# 8_1_BEACON_DRIVER.net
KiCad netlist of a schematic drawn in Altium Designer
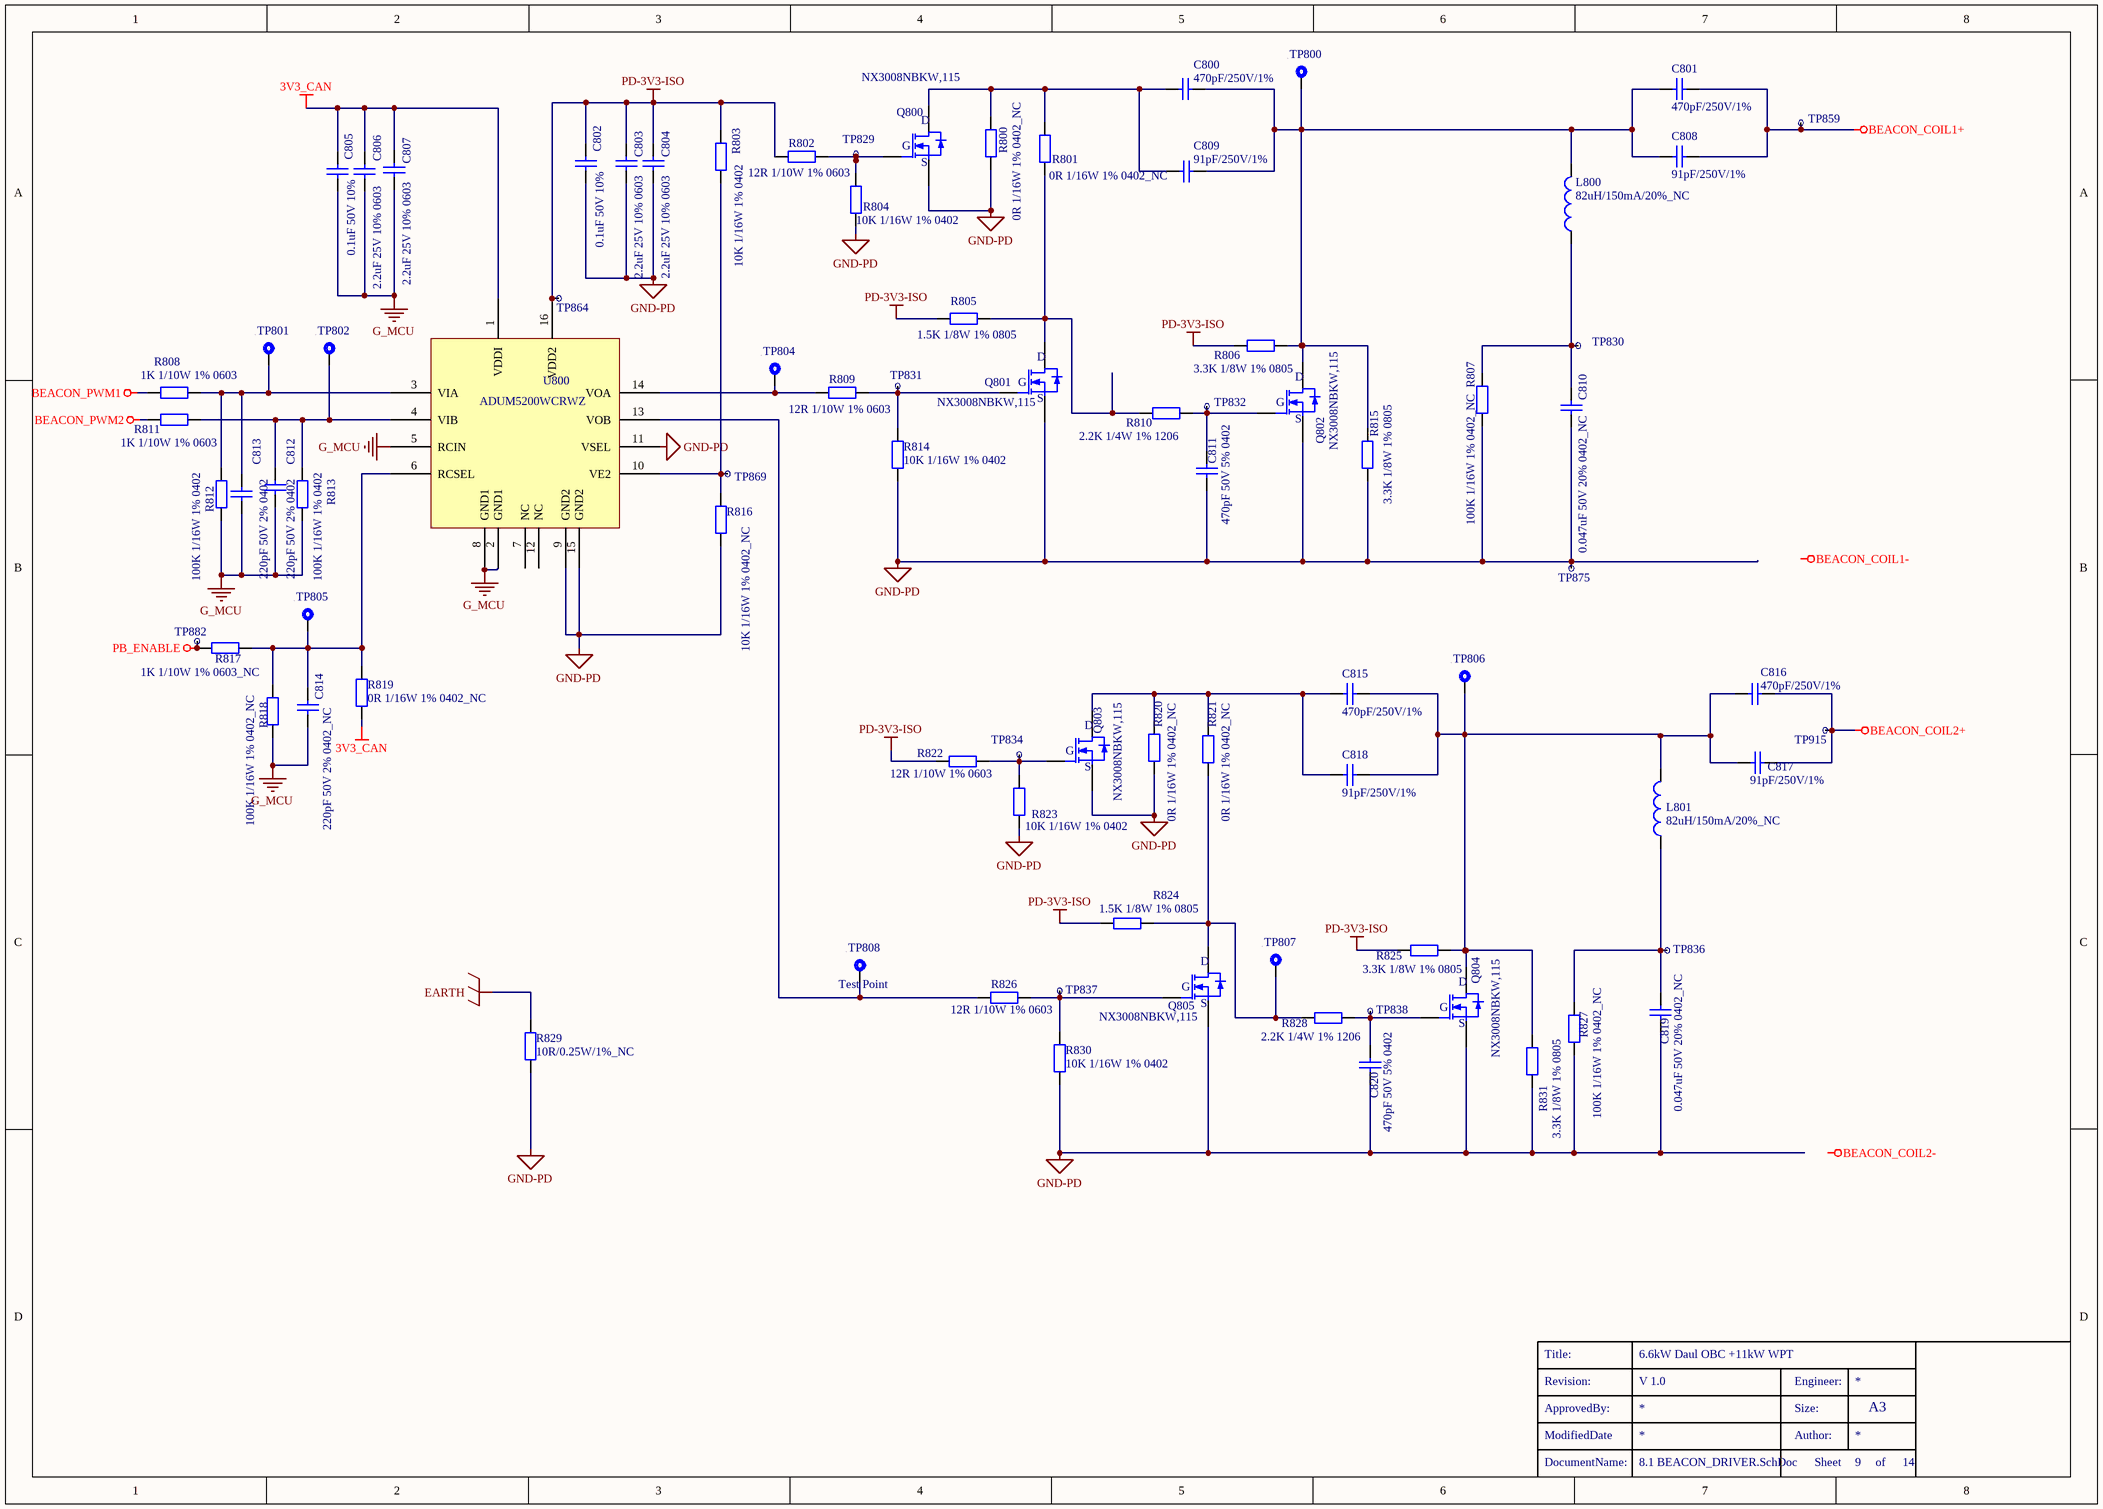
[diagram p0: 8.1 BEACON_DRIVER.SchDoc]

(export (version "E")
  (design (tool "Eeschema 10.0.6"))
  (components
    (comp (ref "C800")
      (value "470pF/250V/1%")
      (footprint "C0603")
      (description "CAP CER 470pF 250V 1% C0G/NP0 0603 SMD")
      (libsource (lib "Miscellaneous Devices") (part "Cap"))
    )
    (comp (ref "C801")
      (value "470pF/250V/1%")
      (footprint "C0603")
      (description "CAP CER 470pF 250V 1% C0G/NP0 0603 SMD")
      (libsource (lib "Miscellaneous Devices") (part "Cap"))
    )
    (comp (ref "C802")
      (value "0.1uF 50V 10%")
      (footprint "C0603")
      (description "CAP CER 0.1uF 50V 10% X7R 0603 SMD")
      (libsource (lib "Miscellaneous Devices") (part "Cap"))
    )
    (comp (ref "C803")
      (value "2.2uF 25V 10% 0603")
      (footprint "C0603")
      (description "CAP CER 2.2uF 25V 10% X5R 0603 SMD")
      (libsource (lib "Miscellaneous Devices") (part "Cap Semi"))
    )
    (comp (ref "C804")
      (value "2.2uF 25V 10% 0603")
      (footprint "C0603")
      (description "CAP CER 2.2uF 25V 10% X5R 0603 SMD")
      (libsource (lib "Miscellaneous Devices") (part "Cap Semi"))
    )
    (comp (ref "C805")
      (value "0.1uF 50V 10%")
      (footprint "C0603")
      (description "CAP CER 0.1uF 50V 10% X7R 0603 SMD")
      (libsource (lib "Miscellaneous Devices") (part "Cap"))
    )
    (comp (ref "C806")
      (value "2.2uF 25V 10% 0603")
      (footprint "C0603")
      (description "CAP CER 2.2uF 25V 10% X5R 0603 SMD")
      (libsource (lib "Miscellaneous Devices") (part "Cap Semi"))
    )
    (comp (ref "C807")
      (value "2.2uF 25V 10% 0603")
      (footprint "C0603")
      (description "CAP CER 2.2uF 25V 10% X5R 0603 SMD")
      (libsource (lib "Miscellaneous Devices") (part "Cap Semi"))
    )
    (comp (ref "C808")
      (value "91pF/250V/1%")
      (footprint "C0603")
      (description "CAP CER 91pF 250V 1% C0G/NP0 0603 SMD")
      (libsource (lib "Miscellaneous Devices") (part "Cap"))
    )
    (comp (ref "C809")
      (value "91pF/250V/1%")
      (footprint "C0603")
      (description "CAP CER 91pF 250V 1% C0G/NP0 0603 SMD")
      (libsource (lib "Miscellaneous Devices") (part "Cap"))
    )
    (comp (ref "C810")
      (value "0.047uF 50V 20% 0402_NC")
      (footprint "C0402")
      (description "CAP CER 0.047uF 50V 20% X7R 0402 SMD")
      (libsource (lib "Miscellaneous Devices") (part "Cap"))
    )
    (comp (ref "C811")
      (value "470pF 50V 5% 0402")
      (footprint "C0402")
      (description "CAP CER 470pF 50V 5% C0G/NP0 0402 SMD")
      (libsource (lib "Miscellaneous Devices") (part "Cap"))
    )
    (comp (ref "C812")
      (value "220pF 50V 2% 0402")
      (footprint "C0402")
      (description "CAP CER 220pF 50V 2% C0G/NPO 0402 SMD")
      (libsource (lib "Miscellaneous Devices") (part "Cap"))
    )
    (comp (ref "C813")
      (value "220pF 50V 2% 0402")
      (footprint "C0402")
      (description "CAP CER 220pF 50V 2% C0G/NPO 0402 SMD")
      (libsource (lib "Miscellaneous Devices") (part "Cap"))
    )
    (comp (ref "C814")
      (value "220pF 50V 2% 0402_NC")
      (footprint "C0402")
      (description "CAP CER 220pF 50V 2% C0G/NPO 0402 SMD")
      (libsource (lib "Miscellaneous Devices") (part "Cap"))
    )
    (comp (ref "C815")
      (value "470pF/250V/1%")
      (footprint "C0603")
      (description "CAP CER 470pF 250V 1% C0G/NP0 0603 SMD")
      (libsource (lib "Miscellaneous Devices") (part "Cap"))
    )
    (comp (ref "C816")
      (value "470pF/250V/1%")
      (footprint "C0603")
      (description "CAP CER 470pF 250V 1% C0G/NP0 0603 SMD")
      (libsource (lib "Miscellaneous Devices") (part "Cap"))
    )
    (comp (ref "C817")
      (value "91pF/250V/1%")
      (footprint "C0603")
      (description "CAP CER 91pF 250V 1% C0G/NP0 0603 SMD")
      (libsource (lib "Miscellaneous Devices") (part "Cap"))
    )
    (comp (ref "C818")
      (value "91pF/250V/1%")
      (footprint "C0603")
      (description "CAP CER 91pF 250V 1% C0G/NP0 0603 SMD")
      (libsource (lib "Miscellaneous Devices") (part "Cap"))
    )
    (comp (ref "C819")
      (value "0.047uF 50V 20% 0402_NC")
      (footprint "C0402")
      (description "CAP CER 0.047uF 50V 20% X7R 0402 SMD")
      (libsource (lib "Miscellaneous Devices") (part "Cap"))
    )
    (comp (ref "C820")
      (value "470pF 50V 5% 0402")
      (footprint "C0402")
      (description "CAP CER 470pF 50V 5% C0G/NP0 0402 SMD")
      (libsource (lib "Miscellaneous Devices") (part "Cap"))
    )
    (comp (ref "L800")
      (value "82uH/150mA/20%_NC")
      (footprint "L2X1.6_0806")
      (description "Inductor 82uH 150mA 20% SMD")
      (libsource (lib "Miscellaneous Devices") (part "Inductor"))
    )
    (comp (ref "L801")
      (value "82uH/150mA/20%_NC")
      (footprint "L2X1.6_0806")
      (description "Inductor 82uH 150mA 20% SMD")
      (libsource (lib "Miscellaneous Devices") (part "Inductor"))
    )
    (comp (ref "Q800")
      (value "NX3008NBKW,115")
      (footprint "SOT323")
      (description "MOSFET N-Channel 30V 350mA SOT-323-3")
      (libsource (lib "N-Channel MOSFET") (part "MOSFET-N"))
    )
    (comp (ref "Q801")
      (value "NX3008NBKW,115")
      (footprint "SOT323")
      (description "MOSFET N-Channel 30V 350mA SOT-323-3")
      (libsource (lib "N-Channel MOSFET") (part "MOSFET-N"))
    )
    (comp (ref "Q802")
      (value "NX3008NBKW,115")
      (footprint "SOT323")
      (description "MOSFET N-Channel 30V 350mA SOT-323-3")
      (libsource (lib "N-Channel MOSFET") (part "MOSFET-N"))
    )
    (comp (ref "Q803")
      (value "NX3008NBKW,115")
      (footprint "SOT323")
      (description "MOSFET N-Channel 30V 350mA SOT-323-3")
      (libsource (lib "N-Channel MOSFET") (part "MOSFET-N"))
    )
    (comp (ref "Q804")
      (value "NX3008NBKW,115")
      (footprint "SOT323")
      (description "MOSFET N-Channel 30V 350mA SOT-323-3")
      (libsource (lib "N-Channel MOSFET") (part "MOSFET-N"))
    )
    (comp (ref "Q805")
      (value "NX3008NBKW,115")
      (footprint "SOT323")
      (description "MOSFET N-Channel 30V 350mA SOT-323-3")
      (libsource (lib "N-Channel MOSFET") (part "MOSFET-N"))
    )
    (comp (ref "R800")
      (value "0R 1/16W 1% 0402_NC")
      (footprint "R0402")
      (description "RES Thick Film 0R 1/16W 1% 0402 SMD")
      (libsource (lib "") (part "Res2_3"))
    )
    (comp (ref "R801")
      (value "0R 1/16W 1% 0402_NC")
      (footprint "R0402")
      (description "RES Thick Film 0R 1/16W 1% 0402 SMD")
      (libsource (lib "") (part "Res2_3"))
    )
    (comp (ref "R802")
      (value "12R 1/10W 1% 0603")
      (footprint "R0603")
      (description "RES Thick Film 12R 1/10W 1% 0603 SMD")
      (libsource (lib "") (part "Res2_1"))
    )
    (comp (ref "R803")
      (value "10K 1/16W 1% 0402")
      (footprint "R0402")
      (description "RES Thick Film 10K 1/16W 1% 0402 SMD")
      (libsource (lib "Miscellaneous Devices") (part "Res2"))
    )
    (comp (ref "R804")
      (value "10K 1/16W 1% 0402")
      (footprint "R0402")
      (description "RES Thick Film 10K 1/16W 1% 0402 SMD")
      (libsource (lib "Miscellaneous Devices") (part "Res2"))
    )
    (comp (ref "R805")
      (value "1.5K 1/8W 1% 0805")
      (footprint "R0805")
      (description "RES Thick Film 1.5K 1/8W 1% 0805 SMD")
      (libsource (lib "") (part "Res2_1"))
    )
    (comp (ref "R806")
      (value "3.3K 1/8W 1% 0805")
      (footprint "R0805")
      (description "RES Thick Film 3.3K 1/8W 1% 0805 SMD")
      (libsource (lib "") (part "Res2_1"))
    )
    (comp (ref "R807")
      (value "100K 1/16W 1% 0402_NC")
      (footprint "R0402")
      (description "RES 100K 1/16W 1% 0402 SMD")
      (libsource (lib "Miscellaneous Devices") (part "Res2"))
    )
    (comp (ref "R808")
      (value "1K 1/10W 1% 0603")
      (footprint "R0603")
      (description "RES Thick Film 1K 1/10W 1% 0603 SMD")
      (libsource (lib "") (part "Res2_2"))
    )
    (comp (ref "R809")
      (value "12R 1/10W 1% 0603")
      (footprint "R0603")
      (description "RES Thick Film 12R 1/10W 1% 0603 SMD")
      (libsource (lib "") (part "Res2_1"))
    )
    (comp (ref "R810")
      (value "2.2K 1/4W 1% 1206")
      (footprint "R1206")
      (description "RES Thick Film 2.2K 1/4W 1% 1206 SMD")
      (libsource (lib "") (part "Res2_1"))
    )
    (comp (ref "R811")
      (value "1K 1/10W 1% 0603")
      (footprint "R0603")
      (description "RES Thick Film 1K 1/10W 1% 0603 SMD")
      (libsource (lib "") (part "Res2_2"))
    )
    (comp (ref "R812")
      (value "100K 1/16W 1% 0402")
      (footprint "R0402")
      (description "RES 100K 1/16W 1% 0402 SMD")
      (libsource (lib "Miscellaneous Devices") (part "Res2"))
    )
    (comp (ref "R813")
      (value "100K 1/16W 1% 0402")
      (footprint "R0402")
      (description "RES 100K 1/16W 1% 0402 SMD")
      (libsource (lib "Miscellaneous Devices") (part "Res2"))
    )
    (comp (ref "R814")
      (value "10K 1/16W 1% 0402")
      (footprint "R0402")
      (description "RES Thick Film 10K 1/16W 1% 0402 SMD")
      (libsource (lib "Miscellaneous Devices") (part "Res2"))
    )
    (comp (ref "R815")
      (value "3.3K 1/8W 1% 0805")
      (footprint "R0805")
      (description "RES Thick Film 3.3K 1/8W 1% 0805 SMD")
      (libsource (lib "Miscellaneous Devices") (part "Res2"))
    )
    (comp (ref "R816")
      (value "10K 1/16W 1% 0402_NC")
      (footprint "R0402")
      (description "RES Thick Film 10K 1/16W 1% 0402 SMD")
      (libsource (lib "Miscellaneous Devices") (part "Res2"))
    )
    (comp (ref "R817")
      (value "1K 1/10W 1% 0603_NC")
      (footprint "R0603")
      (description "RES Thick Film 1K 1/10W 1% 0603 SMD")
      (libsource (lib "") (part "Res2_2"))
    )
    (comp (ref "R818")
      (value "100K 1/16W 1% 0402_NC")
      (footprint "R0402")
      (description "RES 100K 1/16W 1% 0402 SMD")
      (libsource (lib "Miscellaneous Devices") (part "Res2"))
    )
    (comp (ref "R819")
      (value "0R 1/16W 1% 0402_NC")
      (footprint "R0402")
      (description "RES Thick Film 0R 1/16W 1% 0402 SMD")
      (libsource (lib "") (part "Res2_3"))
    )
    (comp (ref "R820")
      (value "0R 1/16W 1% 0402_NC")
      (footprint "R0402")
      (description "RES Thick Film 0R 1/16W 1% 0402 SMD")
      (libsource (lib "") (part "Res2_3"))
    )
    (comp (ref "R821")
      (value "0R 1/16W 1% 0402_NC")
      (footprint "R0402")
      (description "RES Thick Film 0R 1/16W 1% 0402 SMD")
      (libsource (lib "") (part "Res2_3"))
    )
    (comp (ref "R822")
      (value "12R 1/10W 1% 0603")
      (footprint "R0603")
      (description "RES Thick Film 12R 1/10W 1% 0603 SMD")
      (libsource (lib "") (part "Res2_1"))
    )
    (comp (ref "R823")
      (value "10K 1/16W 1% 0402")
      (footprint "R0402")
      (description "RES Thick Film 10K 1/16W 1% 0402 SMD")
      (libsource (lib "Miscellaneous Devices") (part "Res2"))
    )
    (comp (ref "R824")
      (value "1.5K 1/8W 1% 0805")
      (footprint "R0805")
      (description "RES Thick Film 1.5K 1/8W 1% 0805 SMD")
      (libsource (lib "") (part "Res2_1"))
    )
    (comp (ref "R825")
      (value "3.3K 1/8W 1% 0805")
      (footprint "R0805")
      (description "RES Thick Film 3.3K 1/8W 1% 0805 SMD")
      (libsource (lib "") (part "Res2_1"))
    )
    (comp (ref "R826")
      (value "12R 1/10W 1% 0603")
      (footprint "R0603")
      (description "RES Thick Film 12R 1/10W 1% 0603 SMD")
      (libsource (lib "") (part "Res2_1"))
    )
    (comp (ref "R827")
      (value "100K 1/16W 1% 0402_NC")
      (footprint "R0402")
      (description "RES 100K 1/16W 1% 0402 SMD")
      (libsource (lib "Miscellaneous Devices") (part "Res2"))
    )
    (comp (ref "R828")
      (value "2.2K 1/4W 1% 1206")
      (footprint "R1206")
      (description "RES Thick Film 2.2K 1/4W 1% 1206 SMD")
      (libsource (lib "") (part "Res2_1"))
    )
    (comp (ref "R829")
      (value "10R/0.25W/1%_NC")
      (footprint "R1206")
      (description "RES Thick Film 10R 1/4W 1% 1206 SMD")
      (libsource (lib "") (part "Res2_3"))
    )
    (comp (ref "R830")
      (value "10K 1/16W 1% 0402")
      (footprint "R0402")
      (description "RES Thick Film 10K 1/16W 1% 0402 SMD")
      (libsource (lib "Miscellaneous Devices") (part "Res2"))
    )
    (comp (ref "R831")
      (value "3.3K 1/8W 1% 0805")
      (footprint "R0805")
      (description "RES Thick Film 3.3K 1/8W 1% 0805 SMD")
      (libsource (lib "Miscellaneous Devices") (part "Res2"))
    )
    (comp (ref "TP800")
      (value "Test Point")
      (footprint "测试点")
      (description "Test Point 1mm")
      (libsource (lib "Test Point") (part "Test Point"))
    )
    (comp (ref "TP801")
      (value "Test Point")
      (footprint "测试点")
      (description "Test Point 1mm")
      (libsource (lib "Test Point") (part "Test Point"))
    )
    (comp (ref "TP802")
      (value "Test Point")
      (footprint "测试点")
      (description "Test Point 1mm")
      (libsource (lib "Test Point") (part "Test Point"))
    )
    (comp (ref "TP804")
      (value "Test Point")
      (footprint "测试点")
      (description "Test Point 1mm")
      (libsource (lib "Test Point") (part "Test Point"))
    )
    (comp (ref "TP805")
      (value "Test Point")
      (footprint "测试点")
      (description "Test Point 1mm")
      (libsource (lib "Test Point") (part "Test Point"))
    )
    (comp (ref "TP806")
      (value "Test Point")
      (footprint "测试点")
      (description "Test Point 1mm")
      (libsource (lib "Test Point") (part "Test Point"))
    )
    (comp (ref "TP807")
      (value "Test Point")
      (footprint "测试点")
      (description "Test Point 1mm")
      (libsource (lib "Test Point") (part "Test Point"))
    )
    (comp (ref "TP808")
      (value "Test Point")
      (footprint "测试点")
      (description "Test Point 1mm")
      (libsource (lib "Test Point") (part "Test Point"))
    )
    (comp (ref "TP829") (value "测试点") (footprint "测试点") (libsource (lib "原理图符号库2.0") (part "测试点")))
    (comp (ref "TP830") (value "测试点") (footprint "测试点") (libsource (lib "原理图符号库2.0") (part "测试点")))
    (comp (ref "TP831") (value "测试点") (footprint "测试点") (libsource (lib "原理图符号库2.0") (part "测试点")))
    (comp (ref "TP832") (value "测试点") (footprint "测试点") (libsource (lib "原理图符号库2.0") (part "测试点")))
    (comp (ref "TP834") (value "测试点") (footprint "测试点") (libsource (lib "原理图符号库2.0") (part "测试点")))
    (comp (ref "TP836") (value "测试点") (footprint "测试点") (libsource (lib "原理图符号库2.0") (part "测试点")))
    (comp (ref "TP837") (value "测试点") (footprint "测试点") (libsource (lib "原理图符号库2.0") (part "测试点")))
    (comp (ref "TP838") (value "测试点") (footprint "测试点") (libsource (lib "原理图符号库2.0") (part "测试点")))
    (comp (ref "TP859") (value "测试点") (footprint "测试点") (libsource (lib "原理图符号库2.0") (part "测试点")))
    (comp (ref "TP864") (value "测试点") (footprint "测试点") (libsource (lib "原理图符号库2.0") (part "测试点")))
    (comp (ref "TP869") (value "测试点") (footprint "测试点") (libsource (lib "原理图符号库2.0") (part "测试点")))
    (comp (ref "TP875") (value "测试点") (footprint "测试点") (libsource (lib "原理图符号库2.0") (part "测试点")))
    (comp (ref "TP882") (value "测试点") (footprint "测试点") (libsource (lib "原理图符号库2.0") (part "测试点")))
    (comp (ref "TP915") (value "测试点") (footprint "测试点") (libsource (lib "原理图符号库2.0") (part "测试点")))
    (comp (ref "U800")
      (value "ADUM5200WCRWZ")
      (footprint "SOIC-16_L10.3-W7.5-P1.27-LS10.3-BL")
      (description "IC Digital Isolator Integrated DC-DC Dual-Channel 3V-5.5V 23mA SOIC-16")
      (libsource (lib "ADUM5200WCRWZ") (part "ADUM5200WCRWZ"))
    )
  )
  (nets
    (net (code "1") (name "3V3_CAN") (class "Default")
      (node (ref "C805") (pin "2") (pinfunction "2_2") (pintype "passive"))
      (node (ref "C806") (pin "2") (pinfunction "2_2") (pintype "passive"))
      (node (ref "C807") (pin "2") (pinfunction "2_2") (pintype "passive"))
      (node (ref "R819") (pin "2") (pinfunction "2_2") (pintype "passive"))
      (node (ref "U800") (pin "1") (pinfunction "VDDI_1") (pintype "passive"))
    )
    (net (code "2") (name "BEACON_COIL1+") (class "Default")
      (node (ref "C801") (pin "1") (pinfunction "1_1") (pintype "passive"))
      (node (ref "C808") (pin "1") (pinfunction "1_1") (pintype "passive"))
      (node (ref "TP859") (pin "1") (pinfunction "1_1") (pintype "passive"))
    )
    (net (code "4") (name "BEACON_COIL2+") (class "Default")
      (node (ref "C816") (pin "1") (pinfunction "1_1") (pintype "passive"))
      (node (ref "C817") (pin "1") (pinfunction "1_1") (pintype "passive"))
      (node (ref "TP915") (pin "1") (pinfunction "1_1") (pintype "passive"))
    )
    (net (code "6") (name "BEACON_PWM1") (class "Default")
      (node (ref "R808") (pin "1") (pinfunction "1_1") (pintype "passive"))
    )
    (net (code "7") (name "BEACON_PWM2") (class "Default")
      (node (ref "R811") (pin "1") (pinfunction "1_1") (pintype "passive"))
    )
    (net (code "8") (name "EARTH") (class "Default")
      (node (ref "R829") (pin "1") (pinfunction "1_1") (pintype "passive"))
    )
    (net (code "9") (name "GND-PD") (class "Default")
      (node (ref "C802") (pin "1") (pinfunction "1_1") (pintype "passive"))
      (node (ref "C803") (pin "1") (pinfunction "1_1") (pintype "passive"))
      (node (ref "C804") (pin "1") (pinfunction "1_1") (pintype "passive"))
      (node (ref "C810") (pin "2") (pinfunction "2_2") (pintype "passive"))
      (node (ref "C811") (pin "2") (pinfunction "2_2") (pintype "passive"))
      (node (ref "C819") (pin "2") (pinfunction "2_2") (pintype "passive"))
      (node (ref "C820") (pin "2") (pinfunction "2_2") (pintype "passive"))
      (node (ref "Q800") (pin "S") (pinfunction "S_S") (pintype "passive"))
      (node (ref "Q801") (pin "S") (pinfunction "S_S") (pintype "passive"))
      (node (ref "Q802") (pin "S") (pinfunction "S_S") (pintype "passive"))
      (node (ref "Q803") (pin "S") (pinfunction "S_S") (pintype "passive"))
      (node (ref "Q804") (pin "S") (pinfunction "S_S") (pintype "passive"))
      (node (ref "Q805") (pin "S") (pinfunction "S_S") (pintype "passive"))
      (node (ref "R800") (pin "2") (pinfunction "2_2") (pintype "passive"))
      (node (ref "R804") (pin "1") (pinfunction "1_1") (pintype "passive"))
      (node (ref "R807") (pin "1") (pinfunction "1_1") (pintype "passive"))
      (node (ref "R814") (pin "1") (pinfunction "1_1") (pintype "passive"))
      (node (ref "R815") (pin "1") (pinfunction "1_1") (pintype "passive"))
      (node (ref "R816") (pin "1") (pinfunction "1_1") (pintype "passive"))
      (node (ref "R820") (pin "2") (pinfunction "2_2") (pintype "passive"))
      (node (ref "R823") (pin "1") (pinfunction "1_1") (pintype "passive"))
      (node (ref "R827") (pin "1") (pinfunction "1_1") (pintype "passive"))
      (node (ref "R829") (pin "2") (pinfunction "2_2") (pintype "passive"))
      (node (ref "R830") (pin "1") (pinfunction "1_1") (pintype "passive"))
      (node (ref "R831") (pin "1") (pinfunction "1_1") (pintype "passive"))
      (node (ref "TP875") (pin "1") (pinfunction "1_1") (pintype "passive"))
      (node (ref "U800") (pin "11") (pinfunction "VSEL_11") (pintype "passive"))
      (node (ref "U800") (pin "15") (pinfunction "GND2_15") (pintype "passive"))
      (node (ref "U800") (pin "9") (pinfunction "GND2_9") (pintype "passive"))
    )
    (net (code "10") (name "G_MCU") (class "Default")
      (node (ref "C805") (pin "1") (pinfunction "1_1") (pintype "passive"))
      (node (ref "C806") (pin "1") (pinfunction "1_1") (pintype "passive"))
      (node (ref "C807") (pin "1") (pinfunction "1_1") (pintype "passive"))
      (node (ref "C812") (pin "2") (pinfunction "2_2") (pintype "passive"))
      (node (ref "C813") (pin "2") (pinfunction "2_2") (pintype "passive"))
      (node (ref "C814") (pin "2") (pinfunction "2_2") (pintype "passive"))
      (node (ref "R812") (pin "1") (pinfunction "1_1") (pintype "passive"))
      (node (ref "R813") (pin "1") (pinfunction "1_1") (pintype "passive"))
      (node (ref "R818") (pin "1") (pinfunction "1_1") (pintype "passive"))
      (node (ref "U800") (pin "2") (pinfunction "GND1_2") (pintype "passive"))
      (node (ref "U800") (pin "5") (pinfunction "RCIN_5") (pintype "passive"))
      (node (ref "U800") (pin "8") (pinfunction "GND1_8") (pintype "passive"))
    )
    (net (code "11") (name "Net-(C800-Pad1)") (class "Default")
      (node (ref "C800") (pin "1") (pinfunction "1_1") (pintype "passive"))
      (node (ref "C801") (pin "2") (pinfunction "2_2") (pintype "passive"))
      (node (ref "C808") (pin "2") (pinfunction "2_2") (pintype "passive"))
      (node (ref "C809") (pin "1") (pinfunction "1_1") (pintype "passive"))
      (node (ref "L800") (pin "2") (pinfunction "2_2") (pintype "passive"))
      (node (ref "Q802") (pin "D") (pinfunction "D_D") (pintype "passive"))
      (node (ref "R806") (pin "1") (pinfunction "1_1") (pintype "passive"))
      (node (ref "R815") (pin "2") (pinfunction "2_2") (pintype "passive"))
      (node (ref "TP800") (pin "1") (pintype "passive"))
    )
    (net (code "12") (name "Net-(C800-Pad2)") (class "Default")
      (node (ref "C800") (pin "2") (pinfunction "2_2") (pintype "passive"))
      (node (ref "C809") (pin "2") (pinfunction "2_2") (pintype "passive"))
      (node (ref "Q800") (pin "D") (pinfunction "D_D") (pintype "passive"))
      (node (ref "R800") (pin "1") (pinfunction "1_1") (pintype "passive"))
      (node (ref "R801") (pin "1") (pinfunction "1_1") (pintype "passive"))
    )
    (net (code "13") (name "Net-(C810-Pad1)") (class "Default")
      (node (ref "C810") (pin "1") (pinfunction "1_1") (pintype "passive"))
      (node (ref "L800") (pin "1") (pinfunction "1_1") (pintype "passive"))
      (node (ref "R807") (pin "2") (pinfunction "2_2") (pintype "passive"))
      (node (ref "TP830") (pin "1") (pinfunction "1_1") (pintype "passive"))
    )
    (net (code "14") (name "Net-(C811-Pad1)") (class "Default")
      (node (ref "C811") (pin "1") (pinfunction "1_1") (pintype "passive"))
      (node (ref "Q802") (pin "G") (pinfunction "G_G") (pintype "passive"))
      (node (ref "R810") (pin "1") (pinfunction "1_1") (pintype "passive"))
      (node (ref "TP832") (pin "1") (pinfunction "1_1") (pintype "passive"))
    )
    (net (code "15") (name "Net-(C815-Pad1)") (class "Default")
      (node (ref "C815") (pin "1") (pinfunction "1_1") (pintype "passive"))
      (node (ref "C816") (pin "2") (pinfunction "2_2") (pintype "passive"))
      (node (ref "C817") (pin "2") (pinfunction "2_2") (pintype "passive"))
      (node (ref "C818") (pin "1") (pinfunction "1_1") (pintype "passive"))
      (node (ref "L801") (pin "2") (pinfunction "2_2") (pintype "passive"))
      (node (ref "Q804") (pin "D") (pinfunction "D_D") (pintype "passive"))
      (node (ref "R825") (pin "1") (pinfunction "1_1") (pintype "passive"))
      (node (ref "R831") (pin "2") (pinfunction "2_2") (pintype "passive"))
      (node (ref "TP806") (pin "1") (pintype "passive"))
    )
    (net (code "16") (name "Net-(C815-Pad2)") (class "Default")
      (node (ref "C815") (pin "2") (pinfunction "2_2") (pintype "passive"))
      (node (ref "C818") (pin "2") (pinfunction "2_2") (pintype "passive"))
      (node (ref "Q803") (pin "D") (pinfunction "D_D") (pintype "passive"))
      (node (ref "R820") (pin "1") (pinfunction "1_1") (pintype "passive"))
      (node (ref "R821") (pin "1") (pinfunction "1_1") (pintype "passive"))
    )
    (net (code "17") (name "Net-(C819-Pad1)") (class "Default")
      (node (ref "C819") (pin "1") (pinfunction "1_1") (pintype "passive"))
      (node (ref "L801") (pin "1") (pinfunction "1_1") (pintype "passive"))
      (node (ref "R827") (pin "2") (pinfunction "2_2") (pintype "passive"))
      (node (ref "TP836") (pin "1") (pinfunction "1_1") (pintype "passive"))
    )
    (net (code "18") (name "Net-(C820-Pad1)") (class "Default")
      (node (ref "C820") (pin "1") (pinfunction "1_1") (pintype "passive"))
      (node (ref "Q804") (pin "G") (pinfunction "G_G") (pintype "passive"))
      (node (ref "R828") (pin "1") (pinfunction "1_1") (pintype "passive"))
      (node (ref "TP838") (pin "1") (pinfunction "1_1") (pintype "passive"))
    )
    (net (code "19") (name "Net-(Q800-PadG)") (class "Default")
      (node (ref "Q800") (pin "G") (pinfunction "G_G") (pintype "passive"))
      (node (ref "R802") (pin "1") (pinfunction "1_1") (pintype "passive"))
      (node (ref "R804") (pin "2") (pinfunction "2_2") (pintype "passive"))
      (node (ref "TP829") (pin "1") (pinfunction "1_1") (pintype "passive"))
    )
    (net (code "20") (name "Net-(Q801-PadD)") (class "Default")
      (node (ref "Q801") (pin "D") (pinfunction "D_D") (pintype "passive"))
      (node (ref "R801") (pin "2") (pinfunction "2_2") (pintype "passive"))
      (node (ref "R805") (pin "1") (pinfunction "1_1") (pintype "passive"))
      (node (ref "R810") (pin "2") (pinfunction "2_2") (pintype "passive"))
    )
    (net (code "21") (name "Net-(Q801-PadG)") (class "Default")
      (node (ref "Q801") (pin "G") (pinfunction "G_G") (pintype "passive"))
      (node (ref "R809") (pin "1") (pinfunction "1_1") (pintype "passive"))
      (node (ref "R814") (pin "2") (pinfunction "2_2") (pintype "passive"))
      (node (ref "TP831") (pin "1") (pinfunction "1_1") (pintype "passive"))
    )
    (net (code "22") (name "Net-(Q803-PadG)") (class "Default")
      (node (ref "Q803") (pin "G") (pinfunction "G_G") (pintype "passive"))
      (node (ref "R822") (pin "1") (pinfunction "1_1") (pintype "passive"))
      (node (ref "R823") (pin "2") (pinfunction "2_2") (pintype "passive"))
      (node (ref "TP834") (pin "1") (pinfunction "1_1") (pintype "passive"))
    )
    (net (code "23") (name "Net-(Q805-PadD)") (class "Default")
      (node (ref "Q805") (pin "D") (pinfunction "D_D") (pintype "passive"))
      (node (ref "R821") (pin "2") (pinfunction "2_2") (pintype "passive"))
      (node (ref "R824") (pin "1") (pinfunction "1_1") (pintype "passive"))
      (node (ref "R828") (pin "2") (pinfunction "2_2") (pintype "passive"))
      (node (ref "TP807") (pin "1") (pintype "passive"))
    )
    (net (code "24") (name "Net-(Q805-PadG)") (class "Default")
      (node (ref "Q805") (pin "G") (pinfunction "G_G") (pintype "passive"))
      (node (ref "R826") (pin "1") (pinfunction "1_1") (pintype "passive"))
      (node (ref "R830") (pin "2") (pinfunction "2_2") (pintype "passive"))
      (node (ref "TP837") (pin "1") (pinfunction "1_1") (pintype "passive"))
    )
    (net (code "25") (name "Net-(U800-RCSEL)") (class "Default")
      (node (ref "C814") (pin "1") (pinfunction "1_1") (pintype "passive"))
      (node (ref "R817") (pin "2") (pinfunction "2_2") (pintype "passive"))
      (node (ref "R818") (pin "2") (pinfunction "2_2") (pintype "passive"))
      (node (ref "R819") (pin "1") (pinfunction "1_1") (pintype "passive"))
      (node (ref "TP805") (pin "1") (pintype "passive"))
      (node (ref "U800") (pin "6") (pinfunction "RCSEL_6") (pintype "passive"))
    )
    (net (code "26") (name "Net-(U800-VE2)") (class "Default")
      (node (ref "R803") (pin "1") (pinfunction "1_1") (pintype "passive"))
      (node (ref "R816") (pin "2") (pinfunction "2_2") (pintype "passive"))
      (node (ref "TP869") (pin "1") (pinfunction "1_1") (pintype "passive"))
      (node (ref "U800") (pin "10") (pinfunction "VE2_10") (pintype "passive"))
    )
    (net (code "27") (name "Net-(U800-VIA)") (class "Default")
      (node (ref "C813") (pin "1") (pinfunction "1_1") (pintype "passive"))
      (node (ref "R808") (pin "2") (pinfunction "2_2") (pintype "passive"))
      (node (ref "R812") (pin "2") (pinfunction "2_2") (pintype "passive"))
      (node (ref "TP801") (pin "1") (pintype "passive"))
      (node (ref "U800") (pin "3") (pinfunction "VIA_3") (pintype "passive"))
    )
    (net (code "28") (name "Net-(U800-VIB)") (class "Default")
      (node (ref "C812") (pin "1") (pinfunction "1_1") (pintype "passive"))
      (node (ref "R811") (pin "2") (pinfunction "2_2") (pintype "passive"))
      (node (ref "R813") (pin "2") (pinfunction "2_2") (pintype "passive"))
      (node (ref "TP802") (pin "1") (pintype "passive"))
      (node (ref "U800") (pin "4") (pinfunction "VIB_4") (pintype "passive"))
    )
    (net (code "29") (name "Net-(U800-VOA)") (class "Default")
      (node (ref "R809") (pin "2") (pinfunction "2_2") (pintype "passive"))
      (node (ref "TP804") (pin "1") (pintype "passive"))
      (node (ref "U800") (pin "14") (pinfunction "VOA_14") (pintype "passive"))
    )
    (net (code "30") (name "Net-(U800-VOB)") (class "Default")
      (node (ref "R826") (pin "2") (pinfunction "2_2") (pintype "passive"))
      (node (ref "TP808") (pin "1") (pintype "passive"))
      (node (ref "U800") (pin "13") (pinfunction "VOB_13") (pintype "passive"))
    )
    (net (code "31") (name "PB_ENABLE") (class "Default")
      (node (ref "R817") (pin "1") (pinfunction "1_1") (pintype "passive"))
      (node (ref "TP882") (pin "1") (pinfunction "1_1") (pintype "passive"))
    )
    (net (code "32") (name "PD-3V3-ISO") (class "Default")
      (node (ref "C802") (pin "2") (pinfunction "2_2") (pintype "passive"))
      (node (ref "C803") (pin "2") (pinfunction "2_2") (pintype "passive"))
      (node (ref "C804") (pin "2") (pinfunction "2_2") (pintype "passive"))
      (node (ref "R802") (pin "2") (pinfunction "2_2") (pintype "passive"))
      (node (ref "R803") (pin "2") (pinfunction "2_2") (pintype "passive"))
      (node (ref "R805") (pin "2") (pinfunction "2_2") (pintype "passive"))
      (node (ref "R806") (pin "2") (pinfunction "2_2") (pintype "passive"))
      (node (ref "R822") (pin "2") (pinfunction "2_2") (pintype "passive"))
      (node (ref "R824") (pin "2") (pinfunction "2_2") (pintype "passive"))
      (node (ref "R825") (pin "2") (pinfunction "2_2") (pintype "passive"))
      (node (ref "TP864") (pin "1") (pinfunction "1_1") (pintype "passive"))
      (node (ref "U800") (pin "16") (pinfunction "VDD2_16") (pintype "passive"))
    )
    (net (code "33") (name "unconnected-(U800-NC-Pad7)") (class "Default")
      (node (ref "U800") (pin "7") (pinfunction "NC_7") (pintype "passive"))
    )
    (net (code "34") (name "unconnected-(U800-NC-Pad12)") (class "Default")
      (node (ref "U800") (pin "12") (pinfunction "NC_12") (pintype "passive"))
    )
  )
)
